# Clocl.net
KiCad netlist of a schematic drawn in Altium Designer
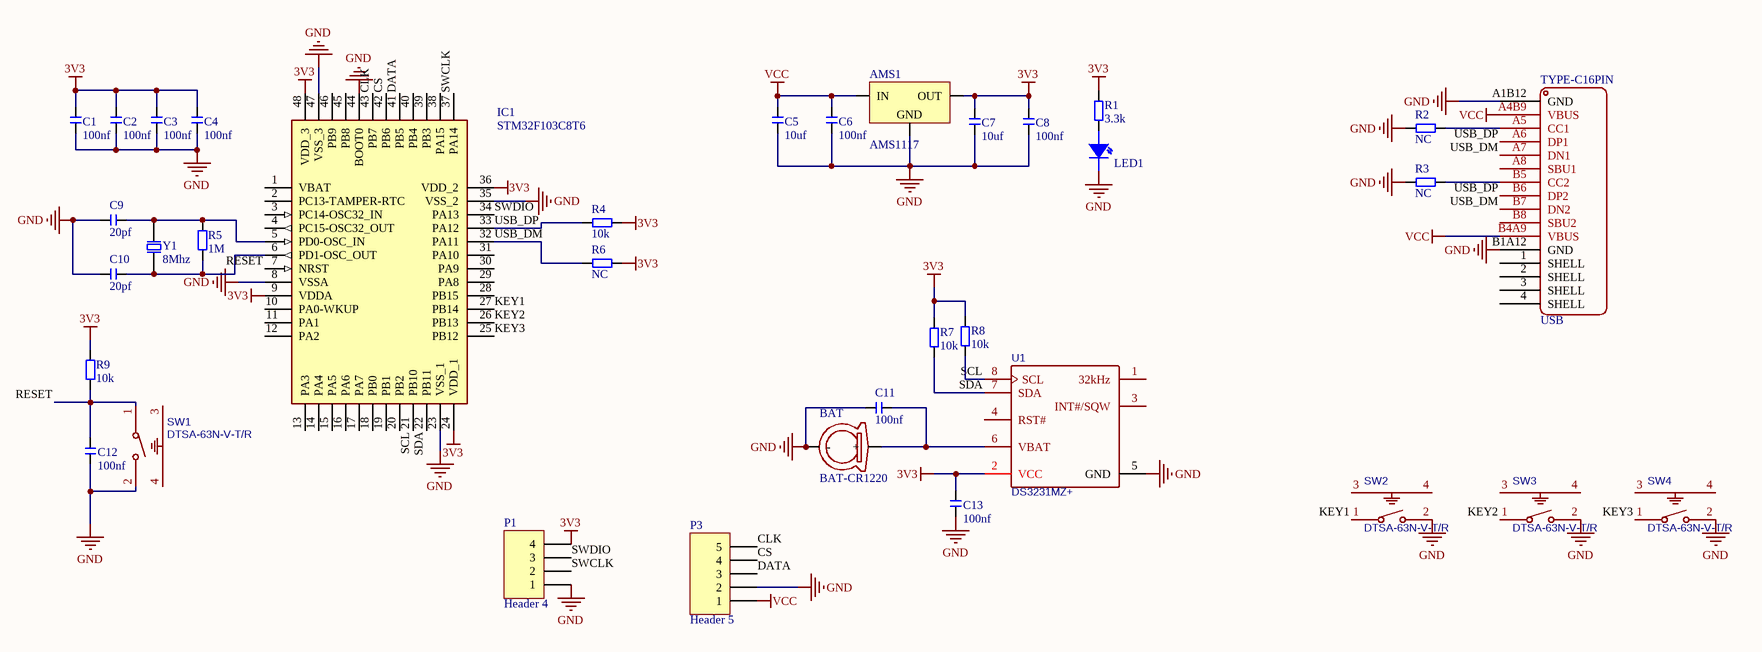
[diagram p0: Clocl.SchDoc]

(export (version "E")
  (design (tool "Eeschema 10.0.6"))
  (components
    (comp (ref "AMS1")
      (value "AMS1117")
      (footprint "SOT223")
      (description "Power")
      (libsource (lib "SWJTUCar") (part "AMS1117"))
    )
    (comp (ref "BAT")
      (value "BAT-CR1220")
      (footprint "BAT-CR1220")
      (libsource (lib "myself") (part "BAT-CR1220"))
    )
    (comp (ref "C1")
      (value "100nf")
      (footprint "C0805")
      (description "无极电容")
      (libsource (lib "SWJTUCar") (part "CAP"))
    )
    (comp (ref "C2")
      (value "100nf")
      (footprint "C0805")
      (description "无极电容")
      (libsource (lib "SWJTUCar") (part "CAP"))
    )
    (comp (ref "C3")
      (value "100nf")
      (footprint "C0805")
      (description "无极电容")
      (libsource (lib "SWJTUCar") (part "CAP"))
    )
    (comp (ref "C4")
      (value "100nf")
      (footprint "C0805")
      (description "无极电容")
      (libsource (lib "SWJTUCar") (part "CAP"))
    )
    (comp (ref "C5")
      (value "10uf")
      (footprint "C0805")
      (description "无极电容")
      (libsource (lib "SWJTUCar") (part "CAP"))
    )
    (comp (ref "C6")
      (value "100nf")
      (footprint "C0805")
      (description "无极电容")
      (libsource (lib "SWJTUCar") (part "CAP"))
    )
    (comp (ref "C7")
      (value "10uf")
      (footprint "C0805")
      (description "无极电容")
      (libsource (lib "SWJTUCar") (part "CAP"))
    )
    (comp (ref "C8")
      (value "100nf")
      (footprint "C0805")
      (description "无极电容")
      (libsource (lib "SWJTUCar") (part "CAP"))
    )
    (comp (ref "C9")
      (value "20pf")
      (footprint "C0805")
      (description "无极电容")
      (libsource (lib "SWJTUCar") (part "CAP"))
    )
    (comp (ref "C10")
      (value "20pf")
      (footprint "C0805")
      (description "无极电容")
      (libsource (lib "SWJTUCar") (part "CAP"))
    )
    (comp (ref "C11")
      (value "100nf")
      (footprint "C0805")
      (description "无极电容")
      (libsource (lib "SWJTUCar") (part "CAP"))
    )
    (comp (ref "C12")
      (value "100nf")
      (footprint "C0805")
      (description "无极电容")
      (libsource (lib "SWJTUCar") (part "CAP"))
    )
    (comp (ref "C13")
      (value "100nf")
      (footprint "C0805")
      (description "无极电容")
      (libsource (lib "SWJTUCar") (part "CAP"))
    )
    (comp (ref "IC1")
      (value "STM32F103C8T6")
      (footprint "QFP50P900X900X160-48N")
      (description "Integrated Circuit")
      (fields
        (field (name "MOUSER PART NUMBER") "511-STM32F103C8T6")
        (field (name "RS PART NUMBER") "0402279P")
      )
      (libsource (lib "myself") (part "STM32F103C8T6"))
    )
    (comp (ref "LED1")
      (value "LED")
      (footprint "LED0603-Orange")
      (description "发光二极管")
      (libsource (lib "SWJTUCar") (part "LED"))
    )
    (comp (ref "P1")
      (value "Header 4")
      (footprint "HDR1X4")
      (description "Header, 4-Pin")
      (fields (field (name "PUBLISHER") "Altium Limited"))
      (libsource (lib "Miscellaneous Connectors") (part "Header 4"))
    )
    (comp (ref "P3")
      (value "Header 5")
      (footprint "HDR1X5")
      (description "Header, 5-Pin")
      (fields (field (name "PUBLISHER") "Altium Limited"))
      (libsource (lib "Miscellaneous Connectors") (part "Header 5"))
    )
    (comp (ref "R1")
      (value "3.3k")
      (footprint "R0805")
      (description "电阻")
      (libsource (lib "SWJTUCar") (part "RES"))
    )
    (comp (ref "R2")
      (value "NC")
      (footprint "R0805")
      (description "电阻")
      (libsource (lib "SWJTUCar") (part "RES"))
    )
    (comp (ref "R3")
      (value "NC")
      (footprint "R0805")
      (description "电阻")
      (libsource (lib "SWJTUCar") (part "RES"))
    )
    (comp (ref "R4")
      (value "10k")
      (footprint "R0805")
      (description "电阻")
      (libsource (lib "SWJTUCar") (part "RES"))
    )
    (comp (ref "R5")
      (value "1M")
      (footprint "R0805")
      (description "电阻")
      (libsource (lib "SWJTUCar") (part "RES"))
    )
    (comp (ref "R6")
      (value "NC")
      (footprint "R0805")
      (description "电阻")
      (libsource (lib "SWJTUCar") (part "RES"))
    )
    (comp (ref "R7")
      (value "10k")
      (footprint "R0805")
      (description "电阻")
      (libsource (lib "SWJTUCar") (part "RES"))
    )
    (comp (ref "R8")
      (value "10k")
      (footprint "R0805")
      (description "电阻")
      (libsource (lib "SWJTUCar") (part "RES"))
    )
    (comp (ref "R9")
      (value "10k")
      (footprint "R0805")
      (description "电阻")
      (libsource (lib "SWJTUCar") (part "RES"))
    )
    (comp (ref "SW1")
      (value "DTSA-63N-V-T/R")
      (footprint "SW-TH_DTSA-63N-V-T/R")
      (fields (field (name "BOM_SUPPLIER PART") "C483865") (field (name "CONTRIBUTOR") "LCSC"))
      (libsource (lib "myself") (part "KEY_ASIDE_DTSA-63N-V-T/R"))
    )
    (comp (ref "SW2")
      (value "DTSA-63N-V-T/R")
      (footprint "SW-TH_DTSA-63N-V-T/R")
      (fields (field (name "BOM_SUPPLIER PART") "C483865") (field (name "CONTRIBUTOR") "LCSC"))
      (libsource (lib "myself") (part "KEY_ASIDE_DTSA-63N-V-T/R"))
    )
    (comp (ref "SW3")
      (value "DTSA-63N-V-T/R")
      (footprint "SW-TH_DTSA-63N-V-T/R")
      (fields (field (name "BOM_SUPPLIER PART") "C483865") (field (name "CONTRIBUTOR") "LCSC"))
      (libsource (lib "myself") (part "KEY_ASIDE_DTSA-63N-V-T/R"))
    )
    (comp (ref "SW4")
      (value "DTSA-63N-V-T/R")
      (footprint "SW-TH_DTSA-63N-V-T/R")
      (fields (field (name "BOM_SUPPLIER PART") "C483865") (field (name "CONTRIBUTOR") "LCSC"))
      (libsource (lib "myself") (part "KEY_ASIDE_DTSA-63N-V-T/R"))
    )
    (comp (ref "TYPE-C16PIN")
      (value "USB")
      (footprint "USB3.0-TYPE-C-SMD_16PIN-H-PITCH0.50")
      (libsource (lib "myself") (part "type-c-16p"))
    )
    (comp (ref "U1")
      (value "DS3231MZ+")
      (footprint "SOIC-8_L4.9-W3.9-P1.27-LS6.0-BL")
      (fields (field (name "BOM_SUPPLIER PART") "C107410"))
      (libsource (lib "myself") (part "DS3231MZ+"))
    )
    (comp (ref "Y1")
      (value "8Mhz")
      (footprint "XTAL_49S-SMD")
      (description "无源晶振")
      (libsource (lib "SWJTUCar") (part "XTAL"))
    )
  )
  (nets
    (net (code "1") (name "/CLK") (class "Default")
      (node (ref "IC1") (pin "43") (pinfunction "PB7_43") (pintype "passive"))
      (node (ref "P3") (pin "5") (pinfunction "5_5") (pintype "passive"))
    )
    (net (code "2") (name "/CS") (class "Default")
      (node (ref "IC1") (pin "42") (pinfunction "PB6_42") (pintype "passive"))
      (node (ref "P3") (pin "4") (pinfunction "4_4") (pintype "passive"))
    )
    (net (code "3") (name "/DATA") (class "Default")
      (node (ref "IC1") (pin "41") (pinfunction "PB5_41") (pintype "passive"))
      (node (ref "P3") (pin "3") (pinfunction "3_3") (pintype "passive"))
    )
    (net (code "4") (name "/KEY1") (class "Default")
      (node (ref "IC1") (pin "27") (pinfunction "PB14_27") (pintype "passive"))
      (node (ref "SW2") (pin "1") (pinfunction "1_1") (pintype "passive"))
    )
    (net (code "5") (name "/KEY2") (class "Default")
      (node (ref "IC1") (pin "26") (pinfunction "PB13_26") (pintype "passive"))
      (node (ref "SW3") (pin "1") (pinfunction "1_1") (pintype "passive"))
    )
    (net (code "6") (name "/KEY3") (class "Default")
      (node (ref "IC1") (pin "25") (pinfunction "PB12_25") (pintype "passive"))
      (node (ref "SW4") (pin "1") (pinfunction "1_1") (pintype "passive"))
    )
    (net (code "7") (name "/RESET") (class "Default")
      (node (ref "C12") (pin "1") (pinfunction "1_1") (pintype "passive"))
      (node (ref "IC1") (pin "7") (pinfunction "NRST_7") (pintype "input"))
      (node (ref "R9") (pin "1") (pinfunction "1_1") (pintype "passive"))
      (node (ref "SW1") (pin "1") (pinfunction "1_1") (pintype "passive"))
    )
    (net (code "8") (name "/SCL") (class "Default")
      (node (ref "IC1") (pin "21") (pinfunction "PB10_21") (pintype "passive"))
      (node (ref "R8") (pin "1") (pinfunction "1_1") (pintype "passive"))
      (node (ref "U1") (pin "8") (pinfunction "SCL_8") (pintype "passive"))
    )
    (net (code "9") (name "/SDA") (class "Default")
      (node (ref "IC1") (pin "22") (pinfunction "PB11_22") (pintype "passive"))
      (node (ref "R7") (pin "1") (pinfunction "1_1") (pintype "passive"))
      (node (ref "U1") (pin "7") (pinfunction "SDA_7") (pintype "passive"))
    )
    (net (code "10") (name "/SWCLK") (class "Default")
      (node (ref "IC1") (pin "37") (pinfunction "PA14_37") (pintype "passive"))
      (node (ref "P1") (pin "2") (pinfunction "2_2") (pintype "passive"))
    )
    (net (code "11") (name "/SWDIO") (class "Default")
      (node (ref "IC1") (pin "34") (pinfunction "PA13_34") (pintype "passive"))
      (node (ref "P1") (pin "3") (pinfunction "3_3") (pintype "passive"))
    )
    (net (code "12") (name "/USB_DM") (class "Default")
      (node (ref "IC1") (pin "32") (pinfunction "PA11_32") (pintype "passive"))
      (node (ref "R6") (pin "2") (pinfunction "2_2") (pintype "passive"))
      (node (ref "TYPE-C16PIN") (pin "A7") (pinfunction "DN1_A7") (pintype "passive"))
      (node (ref "TYPE-C16PIN") (pin "B7") (pinfunction "DN2_B7") (pintype "passive"))
    )
    (net (code "13") (name "/USB_DP") (class "Default")
      (node (ref "IC1") (pin "33") (pinfunction "PA12_33") (pintype "passive"))
      (node (ref "R4") (pin "2") (pinfunction "2_2") (pintype "passive"))
      (node (ref "TYPE-C16PIN") (pin "A6") (pinfunction "DP1_A6") (pintype "passive"))
      (node (ref "TYPE-C16PIN") (pin "B6") (pinfunction "DP2_B6") (pintype "passive"))
    )
    (net (code "14") (name "3V3") (class "Default")
      (node (ref "AMS1") (pin "2") (pinfunction "OUT_2") (pintype "power_in"))
      (node (ref "C1") (pin "1") (pinfunction "1_1") (pintype "passive"))
      (node (ref "C13") (pin "1") (pinfunction "1_1") (pintype "passive"))
      (node (ref "C2") (pin "1") (pinfunction "1_1") (pintype "passive"))
      (node (ref "C3") (pin "1") (pinfunction "1_1") (pintype "passive"))
      (node (ref "C4") (pin "1") (pinfunction "1_1") (pintype "passive"))
      (node (ref "C7") (pin "1") (pinfunction "1_1") (pintype "passive"))
      (node (ref "C8") (pin "1") (pinfunction "1_1") (pintype "passive"))
      (node (ref "IC1") (pin "24") (pinfunction "VDD_1_24") (pintype "power_in"))
      (node (ref "IC1") (pin "36") (pinfunction "VDD_2_36") (pintype "power_in"))
      (node (ref "IC1") (pin "48") (pinfunction "VDD_3_48") (pintype "power_in"))
      (node (ref "IC1") (pin "9") (pinfunction "VDDA_9") (pintype "power_in"))
      (node (ref "P1") (pin "4") (pinfunction "4_4") (pintype "passive"))
      (node (ref "R1") (pin "2") (pinfunction "2_2") (pintype "passive"))
      (node (ref "R4") (pin "1") (pinfunction "1_1") (pintype "passive"))
      (node (ref "R6") (pin "1") (pinfunction "1_1") (pintype "passive"))
      (node (ref "R7") (pin "2") (pinfunction "2_2") (pintype "passive"))
      (node (ref "R8") (pin "2") (pinfunction "2_2") (pintype "passive"))
      (node (ref "R9") (pin "2") (pinfunction "2_2") (pintype "passive"))
      (node (ref "U1") (pin "2") (pinfunction "VCC_2") (pintype "passive"))
    )
    (net (code "15") (name "GND") (class "Default")
      (node (ref "AMS1") (pin "1") (pinfunction "GND_1") (pintype "power_in"))
      (node (ref "BAT") (pin "2") (pinfunction "-_2") (pintype "passive"))
      (node (ref "C1") (pin "2") (pinfunction "2_2") (pintype "passive"))
      (node (ref "C10") (pin "1") (pinfunction "1_1") (pintype "passive"))
      (node (ref "C11") (pin "1") (pinfunction "1_1") (pintype "passive"))
      (node (ref "C12") (pin "2") (pinfunction "2_2") (pintype "passive"))
      (node (ref "C13") (pin "2") (pinfunction "2_2") (pintype "passive"))
      (node (ref "C2") (pin "2") (pinfunction "2_2") (pintype "passive"))
      (node (ref "C3") (pin "2") (pinfunction "2_2") (pintype "passive"))
      (node (ref "C4") (pin "2") (pinfunction "2_2") (pintype "passive"))
      (node (ref "C5") (pin "2") (pinfunction "2_2") (pintype "passive"))
      (node (ref "C6") (pin "2") (pinfunction "2_2") (pintype "passive"))
      (node (ref "C7") (pin "2") (pinfunction "2_2") (pintype "passive"))
      (node (ref "C8") (pin "2") (pinfunction "2_2") (pintype "passive"))
      (node (ref "C9") (pin "1") (pinfunction "1_1") (pintype "passive"))
      (node (ref "IC1") (pin "23") (pinfunction "VSS_1_23") (pintype "power_in"))
      (node (ref "IC1") (pin "35") (pinfunction "VSS_2_35") (pintype "power_in"))
      (node (ref "IC1") (pin "44") (pinfunction "BOOT0_44") (pintype "passive"))
      (node (ref "IC1") (pin "47") (pinfunction "VSS_3_47") (pintype "power_in"))
      (node (ref "IC1") (pin "8") (pinfunction "VSSA_8") (pintype "power_in"))
      (node (ref "LED1") (pin "2") (pinfunction "2_2") (pintype "passive"))
      (node (ref "P1") (pin "1") (pinfunction "1_1") (pintype "passive"))
      (node (ref "P3") (pin "2") (pinfunction "2_2") (pintype "passive"))
      (node (ref "R2") (pin "2") (pinfunction "2_2") (pintype "passive"))
      (node (ref "R3") (pin "2") (pinfunction "2_2") (pintype "passive"))
      (node (ref "SW1") (pin "2") (pinfunction "2_2") (pintype "passive"))
      (node (ref "SW2") (pin "2") (pinfunction "2_2") (pintype "passive"))
      (node (ref "SW3") (pin "2") (pinfunction "2_2") (pintype "passive"))
      (node (ref "SW4") (pin "2") (pinfunction "2_2") (pintype "passive"))
      (node (ref "TYPE-C16PIN") (pin "A1B12") (pinfunction "GND_A1B12") (pintype "passive"))
      (node (ref "TYPE-C16PIN") (pin "B1A12") (pinfunction "GND_B1A12") (pintype "passive"))
      (node (ref "U1") (pin "5") (pinfunction "GND_5") (pintype "passive"))
    )
    (net (code "16") (name "Net-(BAT-+)") (class "Default")
      (node (ref "BAT") (pin "1") (pinfunction "+_1") (pintype "passive"))
      (node (ref "C11") (pin "2") (pinfunction "2_2") (pintype "passive"))
      (node (ref "U1") (pin "6") (pinfunction "VBAT_6") (pintype "passive"))
    )
    (net (code "17") (name "Net-(IC1-PD0-OSC_IN)") (class "Default")
      (node (ref "C9") (pin "2") (pinfunction "2_2") (pintype "passive"))
      (node (ref "IC1") (pin "5") (pinfunction "PD0-OSC_IN_5") (pintype "input"))
      (node (ref "R5") (pin "2") (pinfunction "2_2") (pintype "passive"))
      (node (ref "Y1") (pin "2") (pinfunction "2_2") (pintype "passive"))
    )
    (net (code "18") (name "Net-(IC1-PD1-OSC_OUT)") (class "Default")
      (node (ref "C10") (pin "2") (pinfunction "2_2") (pintype "passive"))
      (node (ref "IC1") (pin "6") (pinfunction "PD1-OSC_OUT_6") (pintype "output"))
      (node (ref "R5") (pin "1") (pinfunction "1_1") (pintype "passive"))
      (node (ref "Y1") (pin "1") (pinfunction "1_1") (pintype "passive"))
    )
    (net (code "19") (name "Net-(LED1-Pad1)") (class "Default")
      (node (ref "LED1") (pin "1") (pinfunction "1_1") (pintype "passive"))
      (node (ref "R1") (pin "1") (pinfunction "1_1") (pintype "passive"))
    )
    (net (code "20") (name "Net-(TYPE-C16PIN-CC1)") (class "Default")
      (node (ref "R2") (pin "1") (pinfunction "1_1") (pintype "passive"))
      (node (ref "TYPE-C16PIN") (pin "A5") (pinfunction "CC1_A5") (pintype "passive"))
    )
    (net (code "21") (name "Net-(TYPE-C16PIN-CC2)") (class "Default")
      (node (ref "R3") (pin "1") (pinfunction "1_1") (pintype "passive"))
      (node (ref "TYPE-C16PIN") (pin "B5") (pinfunction "CC2_B5") (pintype "passive"))
    )
    (net (code "22") (name "VCC") (class "Default")
      (node (ref "AMS1") (pin "3") (pinfunction "IN_3") (pintype "power_in"))
      (node (ref "C5") (pin "1") (pinfunction "1_1") (pintype "passive"))
      (node (ref "C6") (pin "1") (pinfunction "1_1") (pintype "passive"))
      (node (ref "P3") (pin "1") (pinfunction "1_1") (pintype "passive"))
      (node (ref "TYPE-C16PIN") (pin "A4B9") (pinfunction "VBUS_A4B9") (pintype "passive"))
      (node (ref "TYPE-C16PIN") (pin "B4A9") (pinfunction "VBUS_B4A9") (pintype "passive"))
    )
    (net (code "23") (name "unconnected-(IC1-PA0-WKUP-Pad10)") (class "Default")
      (node (ref "IC1") (pin "10") (pinfunction "PA0-WKUP_10") (pintype "passive"))
    )
    (net (code "24") (name "unconnected-(IC1-PA1-Pad11)") (class "Default")
      (node (ref "IC1") (pin "11") (pinfunction "PA1_11") (pintype "passive"))
    )
    (net (code "25") (name "unconnected-(IC1-PA2-Pad12)") (class "Default")
      (node (ref "IC1") (pin "12") (pinfunction "PA2_12") (pintype "passive"))
    )
    (net (code "26") (name "unconnected-(IC1-PA3-Pad13)") (class "Default")
      (node (ref "IC1") (pin "13") (pinfunction "PA3_13") (pintype "passive"))
    )
    (net (code "27") (name "unconnected-(IC1-PA4-Pad14)") (class "Default")
      (node (ref "IC1") (pin "14") (pinfunction "PA4_14") (pintype "passive"))
    )
    (net (code "28") (name "unconnected-(IC1-PA5-Pad15)") (class "Default")
      (node (ref "IC1") (pin "15") (pinfunction "PA5_15") (pintype "passive"))
    )
    (net (code "29") (name "unconnected-(IC1-PA6-Pad16)") (class "Default")
      (node (ref "IC1") (pin "16") (pinfunction "PA6_16") (pintype "passive"))
    )
    (net (code "30") (name "unconnected-(IC1-PA7-Pad17)") (class "Default")
      (node (ref "IC1") (pin "17") (pinfunction "PA7_17") (pintype "passive"))
    )
    (net (code "31") (name "unconnected-(IC1-PA8-Pad29)") (class "Default")
      (node (ref "IC1") (pin "29") (pinfunction "PA8_29") (pintype "passive"))
    )
    (net (code "32") (name "unconnected-(IC1-PA9-Pad30)") (class "Default")
      (node (ref "IC1") (pin "30") (pinfunction "PA9_30") (pintype "passive"))
    )
    (net (code "33") (name "unconnected-(IC1-PA10-Pad31)") (class "Default")
      (node (ref "IC1") (pin "31") (pinfunction "PA10_31") (pintype "passive"))
    )
    (net (code "34") (name "unconnected-(IC1-PA15-Pad38)") (class "Default")
      (node (ref "IC1") (pin "38") (pinfunction "PA15_38") (pintype "passive"))
    )
    (net (code "35") (name "unconnected-(IC1-PB0-Pad18)") (class "Default")
      (node (ref "IC1") (pin "18") (pinfunction "PB0_18") (pintype "passive"))
    )
    (net (code "36") (name "unconnected-(IC1-PB1-Pad19)") (class "Default")
      (node (ref "IC1") (pin "19") (pinfunction "PB1_19") (pintype "passive"))
    )
    (net (code "37") (name "unconnected-(IC1-PB2-Pad20)") (class "Default")
      (node (ref "IC1") (pin "20") (pinfunction "PB2_20") (pintype "passive"))
    )
    (net (code "38") (name "unconnected-(IC1-PB3-Pad39)") (class "Default")
      (node (ref "IC1") (pin "39") (pinfunction "PB3_39") (pintype "passive"))
    )
    (net (code "39") (name "unconnected-(IC1-PB4-Pad40)") (class "Default")
      (node (ref "IC1") (pin "40") (pinfunction "PB4_40") (pintype "passive"))
    )
    (net (code "40") (name "unconnected-(IC1-PB8-Pad45)") (class "Default")
      (node (ref "IC1") (pin "45") (pinfunction "PB8_45") (pintype "passive"))
    )
    (net (code "41") (name "unconnected-(IC1-PB9-Pad46)") (class "Default")
      (node (ref "IC1") (pin "46") (pinfunction "PB9_46") (pintype "passive"))
    )
    (net (code "42") (name "unconnected-(IC1-PB15-Pad28)") (class "Default")
      (node (ref "IC1") (pin "28") (pinfunction "PB15_28") (pintype "passive"))
    )
    (net (code "43") (name "unconnected-(IC1-PC13-TAMPER-RTC-Pad2)") (class "Default")
      (node (ref "IC1") (pin "2") (pinfunction "PC13-TAMPER-RTC_2") (pintype "passive"))
    )
    (net (code "44") (name "unconnected-(IC1-PC14-OSC32_IN-Pad3)") (class "Default")
      (node (ref "IC1") (pin "3") (pinfunction "PC14-OSC32_IN_3") (pintype "input"))
    )
    (net (code "45") (name "unconnected-(IC1-PC15-OSC32_OUT-Pad4)") (class "Default")
      (node (ref "IC1") (pin "4") (pinfunction "PC15-OSC32_OUT_4") (pintype "output"))
    )
    (net (code "46") (name "unconnected-(IC1-VBAT-Pad1)") (class "Default")
      (node (ref "IC1") (pin "1") (pinfunction "VBAT_1") (pintype "passive"))
    )
    (net (code "47") (name "unconnected-(SW1-Pad3)") (class "Default")
      (node (ref "SW1") (pin "3") (pinfunction "3_3") (pintype "passive"))
    )
    (net (code "48") (name "unconnected-(SW1-Pad4)") (class "Default")
      (node (ref "SW1") (pin "4") (pinfunction "4_4") (pintype "passive"))
    )
    (net (code "49") (name "unconnected-(SW2-Pad3)") (class "Default")
      (node (ref "SW2") (pin "3") (pinfunction "3_3") (pintype "passive"))
    )
    (net (code "50") (name "unconnected-(SW2-Pad4)") (class "Default")
      (node (ref "SW2") (pin "4") (pinfunction "4_4") (pintype "passive"))
    )
    (net (code "51") (name "unconnected-(SW3-Pad3)") (class "Default")
      (node (ref "SW3") (pin "3") (pinfunction "3_3") (pintype "passive"))
    )
    (net (code "52") (name "unconnected-(SW3-Pad4)") (class "Default")
      (node (ref "SW3") (pin "4") (pinfunction "4_4") (pintype "passive"))
    )
    (net (code "53") (name "unconnected-(SW4-Pad3)") (class "Default")
      (node (ref "SW4") (pin "3") (pinfunction "3_3") (pintype "passive"))
    )
    (net (code "54") (name "unconnected-(SW4-Pad4)") (class "Default")
      (node (ref "SW4") (pin "4") (pinfunction "4_4") (pintype "passive"))
    )
    (net (code "55") (name "unconnected-(TYPE-C16PIN-SBU1-PadA8)") (class "Default")
      (node (ref "TYPE-C16PIN") (pin "A8") (pinfunction "SBU1_A8") (pintype "passive"))
    )
    (net (code "56") (name "unconnected-(TYPE-C16PIN-SBU2-PadB8)") (class "Default")
      (node (ref "TYPE-C16PIN") (pin "B8") (pinfunction "SBU2_B8") (pintype "passive"))
    )
    (net (code "57") (name "unconnected-(TYPE-C16PIN-SHELL-Pad1)") (class "Default")
      (node (ref "TYPE-C16PIN") (pin "1") (pinfunction "SHELL_1") (pintype "passive"))
    )
    (net (code "58") (name "unconnected-(TYPE-C16PIN-SHELL-Pad2)") (class "Default")
      (node (ref "TYPE-C16PIN") (pin "2") (pinfunction "SHELL_2") (pintype "passive"))
    )
    (net (code "59") (name "unconnected-(TYPE-C16PIN-SHELL-Pad3)") (class "Default")
      (node (ref "TYPE-C16PIN") (pin "3") (pinfunction "SHELL_3") (pintype "passive"))
    )
    (net (code "60") (name "unconnected-(TYPE-C16PIN-SHELL-Pad4)") (class "Default")
      (node (ref "TYPE-C16PIN") (pin "4") (pinfunction "SHELL_4") (pintype "passive"))
    )
    (net (code "61") (name "unconnected-(U1-32kHz-Pad1)") (class "Default")
      (node (ref "U1") (pin "1") (pinfunction "32kHz_1") (pintype "passive"))
    )
    (net (code "62") (name "unconnected-(U1-INT#{slash}SQW-Pad3)") (class "Default")
      (node (ref "U1") (pin "3") (pinfunction "INT#/SQW_3") (pintype "passive"))
    )
    (net (code "63") (name "unconnected-(U1-RST#-Pad4)") (class "Default")
      (node (ref "U1") (pin "4") (pinfunction "RST#_4") (pintype "passive"))
    )
  )
)
